# MAGI_sBuckPower-TEST.net
KiCad netlist of a schematic drawn in Altium Designer
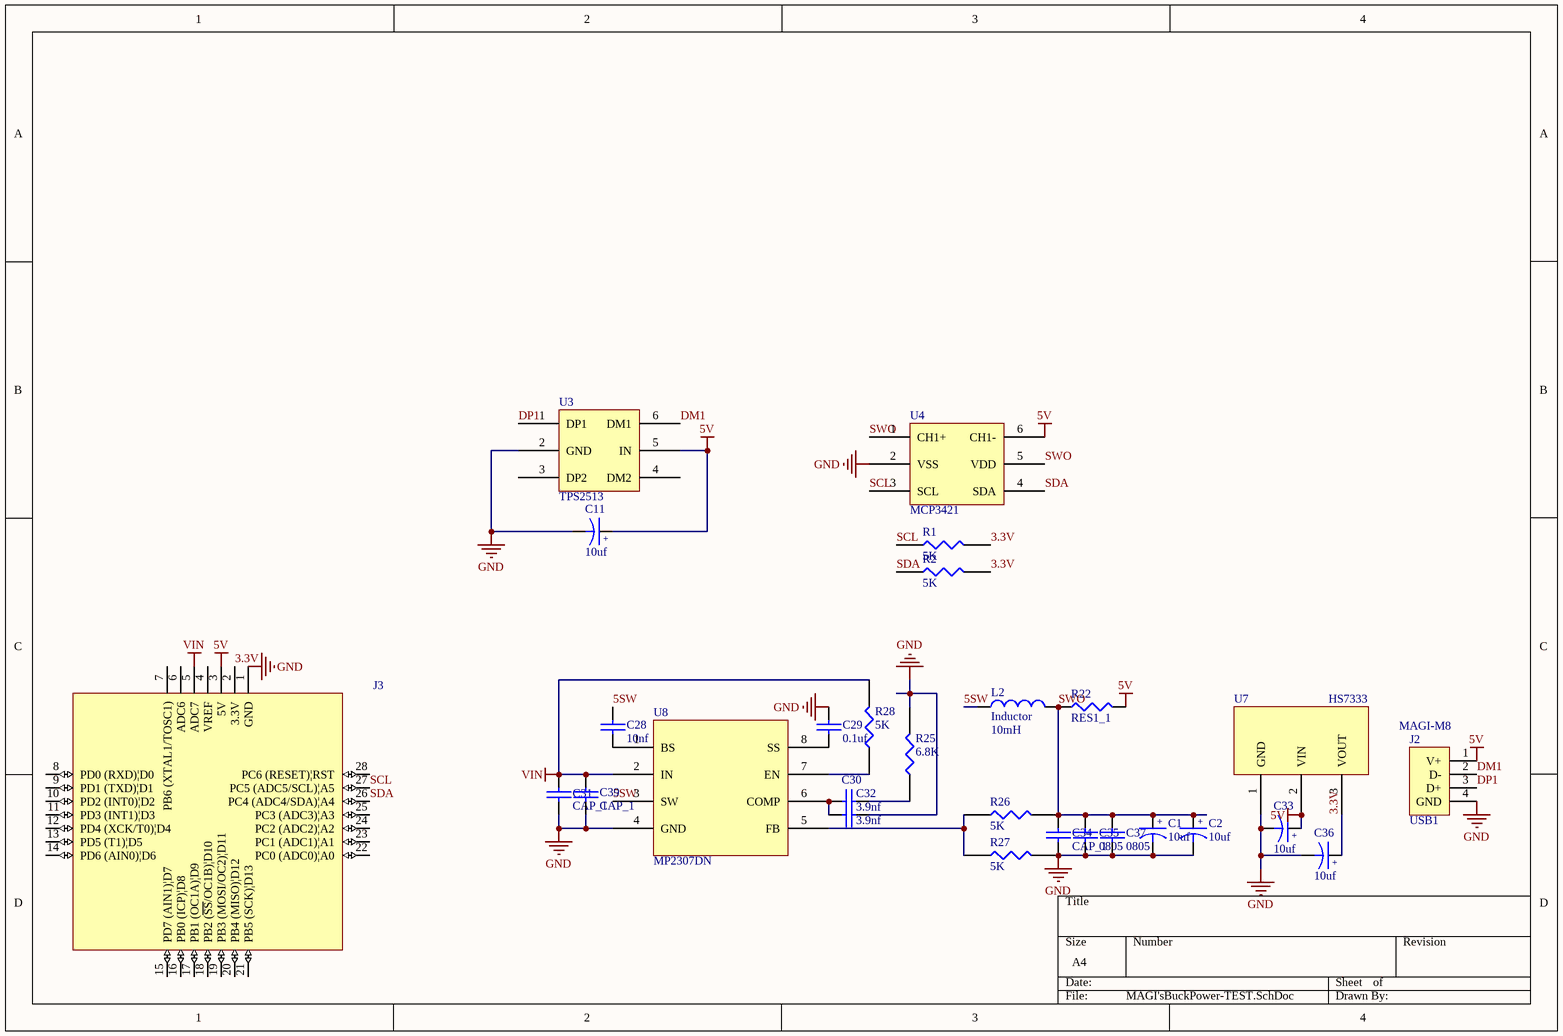
[diagram p0: MAGI'sBuckPower-TEST.SchDoc]

(export (version "E")
  (design (tool "Eeschema 10.0.6"))
  (components
    (comp (ref "C1")
      (value "10uf")
      (footprint "C1210_N")
      (description "Capacitor")
      (libsource (lib "电容器") (part "CAPACITOR POL"))
    )
    (comp (ref "C2")
      (value "10uf")
      (footprint "C1210_N")
      (description "Capacitor")
      (libsource (lib "电容器") (part "CAPACITOR POL"))
    )
    (comp (ref "C11")
      (value "10uf")
      (footprint "6-0805_N")
      (description "Capacitor")
      (libsource (lib "电容器") (part "CAPACITOR POL"))
    )
    (comp (ref "C28")
      (value "10nf")
      (footprint "6-0805_N")
      (description "Capacitor")
      (libsource (lib "电容器") (part "CAP_1"))
    )
    (comp (ref "C29")
      (value "0.1uf")
      (footprint "6-0805_N")
      (description "Capacitor")
      (libsource (lib "电容器") (part "CAP_1"))
    )
    (comp (ref "C30")
      (value "3.9nf")
      (footprint "6-0805_N")
      (description "Capacitor")
      (libsource (lib "电容器") (part "CAP_1"))
    )
    (comp (ref "C31")
      (value "CAP_1")
      (footprint "C1206")
      (description "Capacitor")
      (libsource (lib "电容器") (part "CAP_1"))
    )
    (comp (ref "C32")
      (value "3.9nf")
      (footprint "6-0805_N")
      (description "Capacitor")
      (libsource (lib "电容器") (part "CAP_1"))
    )
    (comp (ref "C33")
      (value "10uf")
      (footprint "6-0805_N")
      (description "Capacitor")
      (libsource (lib "电容器") (part "CAPACITOR POL"))
    )
    (comp (ref "C34")
      (value "CAP_1")
      (footprint "6TPE330M")
      (description "Capacitor")
      (libsource (lib "电容器") (part "CAP_1"))
    )
    (comp (ref "C35")
      (value "0805")
      (footprint "6-0805_N")
      (description "Capacitor")
      (libsource (lib "电容器") (part "CAP_1"))
    )
    (comp (ref "C36")
      (value "10uf")
      (footprint "6-0805_N")
      (description "Capacitor")
      (libsource (lib "电容器") (part "CAPACITOR POL"))
    )
    (comp (ref "C37")
      (value "0805")
      (footprint "6-0805_N")
      (description "Capacitor")
      (libsource (lib "电容器") (part "CAP_1"))
    )
    (comp (ref "C39")
      (value "CAP_1")
      (footprint "C1206")
      (description "Capacitor")
      (libsource (lib "电容器") (part "CAP_1"))
    )
    (comp (ref "J2") (value "USB1") (footprint "USB-04A") (libsource (lib "USB接口") (part "USB1")))
    (comp (ref "J3") (value "MAGI-M8") (footprint "MAGIsBoard") (libsource (lib "MAGI-M8") (part "MAGI-M8")))
    (comp (ref "L2")
      (value "Inductor")
      (footprint "7*7")
      (fields (field (name "ALTIUM_VALUE") "10mH") (field (name "PUBLISHER") "Altium Limited"))
      (libsource (lib "Miscellaneous Devices") (part "Inductor"))
    )
    (comp (ref "R1") (value "5K") (footprint "6-0805_N") (libsource (lib "电阻器") (part "RES1")))
    (comp (ref "R2") (value "5K") (footprint "6-0805_N") (libsource (lib "电阻器") (part "RES1")))
    (comp (ref "R22") (value "RES1_1") (footprint "2512") (libsource (lib "电阻器") (part "RES1_1")))
    (comp (ref "R25") (value "6.8K") (footprint "6-0805_N") (libsource (lib "电阻器") (part "RES1")))
    (comp (ref "R26") (value "5K") (footprint "6-0805_N") (libsource (lib "电阻器") (part "RES1")))
    (comp (ref "R27") (value "5K") (footprint "6-0805_N") (libsource (lib "电阻器") (part "RES1")))
    (comp (ref "R28") (value "5K") (footprint "6-0805_N") (libsource (lib "电阻器") (part "RES1")))
    (comp (ref "U3") (value "TPS2513") (footprint "TPS2513") (libsource (lib "PMIC") (part "TPS2513")))
    (comp (ref "U4") (value "MCP3421") (footprint "tps2513") (libsource (lib "ADC") (part "MCP3421")))
    (comp (ref "U7") (value "HS7333") (footprint "HS7333") (libsource (lib "PMIC") (part "HS7333")))
    (comp (ref "U8")
      (value "MP2307DN")
      (footprint "MP2307DN")
      (libsource (lib "MP2307Test") (part "MP2307DN"))
    )
  )
  (nets
    (net (code "1") (name "/3.3V") (class "Default")
      (node (ref "C36") (pin "1") (pinfunction "1_1") (pintype "passive"))
      (node (ref "J3") (pin "2") (pinfunction "3.3V_2") (pintype "power_in"))
      (node (ref "R1") (pin "2") (pinfunction "2_2") (pintype "passive"))
      (node (ref "R2") (pin "2") (pinfunction "2_2") (pintype "passive"))
      (node (ref "U7") (pin "3") (pinfunction "VOUT_3") (pintype "passive"))
    )
    (net (code "2") (name "/5SW") (class "Default")
      (node (ref "C28") (pin "1") (pinfunction "1_1") (pintype "passive"))
      (node (ref "L2") (pin "1") (pinfunction "1_1") (pintype "passive"))
      (node (ref "U8") (pin "3") (pinfunction "SW_3") (pintype "passive"))
    )
    (net (code "3") (name "/DM1") (class "Default")
      (node (ref "J2") (pin "2") (pinfunction "D-_2") (pintype "passive"))
      (node (ref "U3") (pin "6") (pinfunction "DM1_6") (pintype "passive"))
    )
    (net (code "4") (name "/DP1") (class "Default")
      (node (ref "J2") (pin "3") (pinfunction "D+_3") (pintype "passive"))
      (node (ref "U3") (pin "1") (pinfunction "DP1_1") (pintype "passive"))
    )
    (net (code "5") (name "/SCL") (class "Default")
      (node (ref "J3") (pin "27") (pinfunction "PC5_(ADC5/SCL)¦A5_27") (pintype "bidirectional"))
      (node (ref "R1") (pin "1") (pinfunction "1_1") (pintype "passive"))
      (node (ref "U4") (pin "3") (pinfunction "SCL_3") (pintype "passive"))
    )
    (net (code "6") (name "/SDA") (class "Default")
      (node (ref "J3") (pin "26") (pinfunction "PC4_(ADC4/SDA)¦A4_26") (pintype "bidirectional"))
      (node (ref "R2") (pin "1") (pinfunction "1_1") (pintype "passive"))
      (node (ref "U4") (pin "4") (pinfunction "SDA_4") (pintype "passive"))
    )
    (net (code "7") (name "/SWO") (class "Default")
      (node (ref "C1") (pin "1") (pinfunction "1_1") (pintype "passive"))
      (node (ref "C2") (pin "1") (pinfunction "1_1") (pintype "passive"))
      (node (ref "C34") (pin "1") (pinfunction "1_1") (pintype "passive"))
      (node (ref "C35") (pin "1") (pinfunction "1_1") (pintype "passive"))
      (node (ref "C37") (pin "1") (pinfunction "1_1") (pintype "passive"))
      (node (ref "L2") (pin "2") (pinfunction "2_2") (pintype "passive"))
      (node (ref "R22") (pin "1") (pinfunction "1_1") (pintype "passive"))
      (node (ref "R26") (pin "2") (pinfunction "2_2") (pintype "passive"))
      (node (ref "U4") (pin "1") (pinfunction "CH1+_1") (pintype "passive"))
      (node (ref "U4") (pin "5") (pinfunction "VDD_5") (pintype "passive"))
    )
    (net (code "8") (name "5V") (class "Default")
      (node (ref "C11") (pin "1") (pinfunction "1_1") (pintype "passive"))
      (node (ref "C33") (pin "1") (pinfunction "1_1") (pintype "passive"))
      (node (ref "J2") (pin "1") (pinfunction "V+_1") (pintype "passive"))
      (node (ref "J3") (pin "3") (pinfunction "5V_3") (pintype "power_in"))
      (node (ref "R22") (pin "2") (pinfunction "2_2") (pintype "passive"))
      (node (ref "U3") (pin "5") (pinfunction "IN_5") (pintype "passive"))
      (node (ref "U4") (pin "6") (pinfunction "CH1-_6") (pintype "passive"))
      (node (ref "U7") (pin "2") (pinfunction "VIN_2") (pintype "passive"))
    )
    (net (code "9") (name "GND") (class "Default")
      (node (ref "C1") (pin "2") (pinfunction "2_2") (pintype "passive"))
      (node (ref "C11") (pin "2") (pinfunction "2_2") (pintype "passive"))
      (node (ref "C2") (pin "2") (pinfunction "2_2") (pintype "passive"))
      (node (ref "C29") (pin "1") (pinfunction "1_1") (pintype "passive"))
      (node (ref "C31") (pin "2") (pinfunction "2_2") (pintype "passive"))
      (node (ref "C32") (pin "2") (pinfunction "2_2") (pintype "passive"))
      (node (ref "C33") (pin "2") (pinfunction "2_2") (pintype "passive"))
      (node (ref "C34") (pin "2") (pinfunction "2_2") (pintype "passive"))
      (node (ref "C35") (pin "2") (pinfunction "2_2") (pintype "passive"))
      (node (ref "C36") (pin "2") (pinfunction "2_2") (pintype "passive"))
      (node (ref "C37") (pin "2") (pinfunction "2_2") (pintype "passive"))
      (node (ref "C39") (pin "2") (pinfunction "2_2") (pintype "passive"))
      (node (ref "J2") (pin "4") (pinfunction "GND_4") (pintype "passive"))
      (node (ref "J3") (pin "1") (pinfunction "GND_1") (pintype "power_in"))
      (node (ref "R25") (pin "2") (pinfunction "2_2") (pintype "passive"))
      (node (ref "R27") (pin "2") (pinfunction "2_2") (pintype "passive"))
      (node (ref "U3") (pin "2") (pinfunction "GND_2") (pintype "passive"))
      (node (ref "U4") (pin "2") (pinfunction "VSS_2") (pintype "passive"))
      (node (ref "U7") (pin "1") (pinfunction "GND_1") (pintype "passive"))
      (node (ref "U8") (pin "4") (pinfunction "GND_4") (pintype "passive"))
    )
    (net (code "10") (name "Net-(C30-Pad2)") (class "Default")
      (node (ref "C30") (pin "2") (pinfunction "2_2") (pintype "passive"))
      (node (ref "R25") (pin "1") (pinfunction "1_1") (pintype "passive"))
    )
    (net (code "11") (name "Net-(U8-BS)") (class "Default")
      (node (ref "C28") (pin "2") (pinfunction "2_2") (pintype "passive"))
      (node (ref "U8") (pin "1") (pinfunction "BS_1") (pintype "passive"))
    )
    (net (code "12") (name "Net-(U8-COMP)") (class "Default")
      (node (ref "C30") (pin "1") (pinfunction "1_1") (pintype "passive"))
      (node (ref "C32") (pin "1") (pinfunction "1_1") (pintype "passive"))
      (node (ref "U8") (pin "6") (pinfunction "COMP_6") (pintype "passive"))
    )
    (net (code "13") (name "Net-(U8-EN)") (class "Default")
      (node (ref "R28") (pin "1") (pinfunction "1_1") (pintype "passive"))
      (node (ref "U8") (pin "7") (pinfunction "EN_7") (pintype "passive"))
    )
    (net (code "14") (name "Net-(U8-FB)") (class "Default")
      (node (ref "R26") (pin "1") (pinfunction "1_1") (pintype "passive"))
      (node (ref "R27") (pin "1") (pinfunction "1_1") (pintype "passive"))
      (node (ref "U8") (pin "5") (pinfunction "FB_5") (pintype "passive"))
    )
    (net (code "15") (name "Net-(U8-SS)") (class "Default")
      (node (ref "C29") (pin "2") (pinfunction "2_2") (pintype "passive"))
      (node (ref "U8") (pin "8") (pinfunction "SS_8") (pintype "passive"))
    )
    (net (code "16") (name "VIN") (class "Default")
      (node (ref "C31") (pin "1") (pinfunction "1_1") (pintype "passive"))
      (node (ref "C39") (pin "1") (pinfunction "1_1") (pintype "passive"))
      (node (ref "J3") (pin "5") (pinfunction "ADC7_5") (pintype "passive"))
      (node (ref "R28") (pin "2") (pinfunction "2_2") (pintype "passive"))
      (node (ref "U8") (pin "2") (pinfunction "IN_2") (pintype "passive"))
    )
    (net (code "17") (name "unconnected-(J3-ADC6-Pad6)") (class "Default")
      (node (ref "J3") (pin "6") (pinfunction "ADC6_6") (pintype "passive"))
    )
    (net (code "18") (name "unconnected-(J3-PB0_(ICP)¦D8-Pad16)") (class "Default")
      (node (ref "J3") (pin "16") (pinfunction "PB0_(ICP)¦D8_16") (pintype "bidirectional"))
    )
    (net (code "19") (name "unconnected-(J3-PB1_(OC1A)¦D9-Pad17)") (class "Default")
      (node (ref "J3") (pin "17") (pinfunction "PB1_(OC1A)¦D9_17") (pintype "bidirectional"))
    )
    (net (code "20") (name "unconnected-(J3-PB2_(~{SS}{slash}OC1B)¦D10-Pad18)") (class "Default")
      (node (ref "J3") (pin "18") (pinfunction "PB2_(~{SS}/OC1B)¦D10_18") (pintype "bidirectional"))
    )
    (net (code "21") (name "unconnected-(J3-PB3_(MOSI{slash}OC2)¦D11-Pad19)") (class "Default")
      (node (ref "J3") (pin "19") (pinfunction "PB3_(MOSI/OC2)¦D11_19") (pintype "bidirectional"))
    )
    (net (code "22") (name "unconnected-(J3-PB4_(MISO)¦D12-Pad20)") (class "Default")
      (node (ref "J3") (pin "20") (pinfunction "PB4_(MISO)¦D12_20") (pintype "bidirectional"))
    )
    (net (code "23") (name "unconnected-(J3-PB5_(SCK)¦D13-Pad21)") (class "Default")
      (node (ref "J3") (pin "21") (pinfunction "PB5_(SCK)¦D13_21") (pintype "bidirectional"))
    )
    (net (code "24") (name "unconnected-(J3-PB6_(XTAL1{slash}TOSC1)-Pad7)") (class "Default")
      (node (ref "J3") (pin "7") (pinfunction "PB6_(XTAL1/TOSC1)_7") (pintype "passive"))
    )
    (net (code "25") (name "unconnected-(J3-PC0_(ADC0)¦A0-Pad22)") (class "Default")
      (node (ref "J3") (pin "22") (pinfunction "PC0_(ADC0)¦A0_22") (pintype "bidirectional"))
    )
    (net (code "26") (name "unconnected-(J3-PC1_(ADC1)¦A1-Pad23)") (class "Default")
      (node (ref "J3") (pin "23") (pinfunction "PC1_(ADC1)¦A1_23") (pintype "bidirectional"))
    )
    (net (code "27") (name "unconnected-(J3-PC2_(ADC2)¦A2-Pad24)") (class "Default")
      (node (ref "J3") (pin "24") (pinfunction "PC2_(ADC2)¦A2_24") (pintype "bidirectional"))
    )
    (net (code "28") (name "unconnected-(J3-PC3_(ADC3)¦A3-Pad25)") (class "Default")
      (node (ref "J3") (pin "25") (pinfunction "PC3_(ADC3)¦A3_25") (pintype "bidirectional"))
    )
    (net (code "29") (name "unconnected-(J3-PC6_(RESET)¦RST-Pad28)") (class "Default")
      (node (ref "J3") (pin "28") (pinfunction "PC6_(RESET)¦RST_28") (pintype "bidirectional"))
    )
    (net (code "30") (name "unconnected-(J3-PD0_(RXD)¦D0-Pad8)") (class "Default")
      (node (ref "J3") (pin "8") (pinfunction "PD0_(RXD)¦D0_8") (pintype "bidirectional"))
    )
    (net (code "31") (name "unconnected-(J3-PD1_(TXD)¦D1-Pad9)") (class "Default")
      (node (ref "J3") (pin "9") (pinfunction "PD1_(TXD)¦D1_9") (pintype "bidirectional"))
    )
    (net (code "32") (name "unconnected-(J3-PD2_(INT0)¦D2-Pad10)") (class "Default")
      (node (ref "J3") (pin "10") (pinfunction "PD2_(INT0)¦D2_10") (pintype "bidirectional"))
    )
    (net (code "33") (name "unconnected-(J3-PD3_(INT1)¦D3-Pad11)") (class "Default")
      (node (ref "J3") (pin "11") (pinfunction "PD3_(INT1)¦D3_11") (pintype "bidirectional"))
    )
    (net (code "34") (name "unconnected-(J3-PD4_(XCK{slash}T0)¦D4-Pad12)") (class "Default")
      (node (ref "J3") (pin "12") (pinfunction "PD4_(XCK/T0)¦D4_12") (pintype "bidirectional"))
    )
    (net (code "35") (name "unconnected-(J3-PD5_(T1)¦D5-Pad13)") (class "Default")
      (node (ref "J3") (pin "13") (pinfunction "PD5_(T1)¦D5_13") (pintype "bidirectional"))
    )
    (net (code "36") (name "unconnected-(J3-PD6_(AIN0)¦D6-Pad14)") (class "Default")
      (node (ref "J3") (pin "14") (pinfunction "PD6_(AIN0)¦D6_14") (pintype "bidirectional"))
    )
    (net (code "37") (name "unconnected-(J3-PD7_(AIN1)¦D7-Pad15)") (class "Default")
      (node (ref "J3") (pin "15") (pinfunction "PD7_(AIN1)¦D7_15") (pintype "bidirectional"))
    )
    (net (code "38") (name "unconnected-(J3-VREF-Pad4)") (class "Default")
      (node (ref "J3") (pin "4") (pinfunction "VREF_4") (pintype "passive"))
    )
    (net (code "39") (name "unconnected-(U3-DM2-Pad4)") (class "Default")
      (node (ref "U3") (pin "4") (pinfunction "DM2_4") (pintype "passive"))
    )
    (net (code "40") (name "unconnected-(U3-DP2-Pad3)") (class "Default")
      (node (ref "U3") (pin "3") (pinfunction "DP2_3") (pintype "passive"))
    )
  )
)
